# 4024_bin_counter.net
KiCad netlist of a schematic drawn in EAGLE
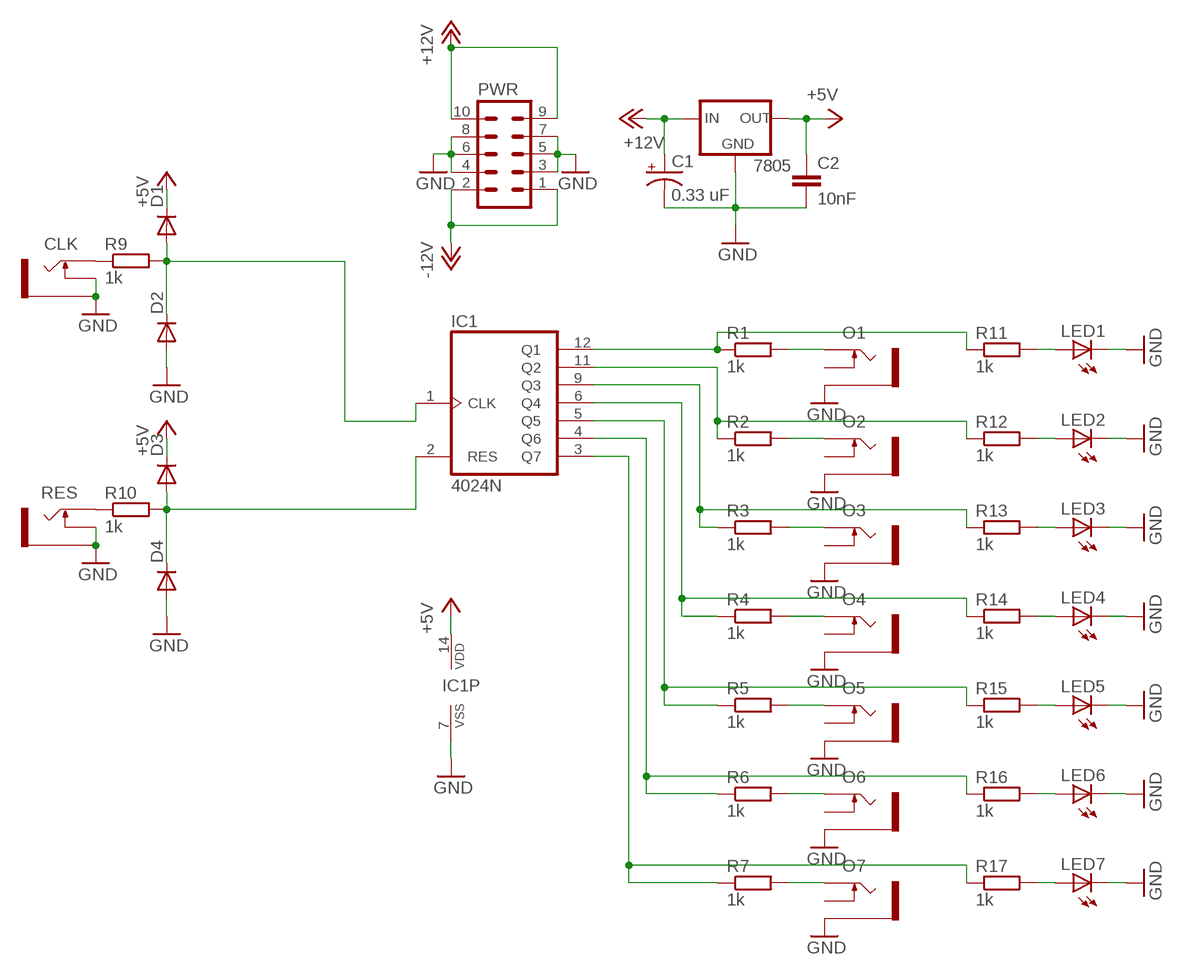
[diagram p0: schematic, sheet 1]

(export (version "E")
  (design (tool "Eeschema 10.0.6"))
  (components
    (comp (ref "7805")
      (value "78XXS")
      (footprint "eagle-import:78XXS")
      (libsource (lib "eagle-import") (part "78XXS"))
    )
    (comp (ref "C1")
      (value "0.33 uF")
      (footprint "eagle-import:E2,5-7")
      (libsource (lib "eagle-import") (part "CPOL-USE2.5-7"))
    )
    (comp (ref "C2")
      (value "10nF")
      (footprint "eagle-import:CAP-PTH-10MM")
      (libsource (lib "eagle-import") (part "10NF-PTH-10MM-10000V-1-%"))
    )
    (comp (ref "CLK")
      (value "THONKICONNNEW")
      (footprint "eagle-import:WQP-PJ301M-12_JACK")
      (libsource (lib "eagle-import") (part "THONKICONNNEW"))
    )
    (comp (ref "D1")
      (value "SMALL_DIODEDO35-7")
      (footprint "eagle-import:DO35-7")
      (libsource (lib "eagle-import") (part "SMALL_DIODEDO35-7"))
    )
    (comp (ref "D2")
      (value "SMALL_DIODEDO35-7")
      (footprint "eagle-import:DO35-7")
      (libsource (lib "eagle-import") (part "SMALL_DIODEDO35-7"))
    )
    (comp (ref "D3")
      (value "SMALL_DIODEDO35-7")
      (footprint "eagle-import:DO35-7")
      (libsource (lib "eagle-import") (part "SMALL_DIODEDO35-7"))
    )
    (comp (ref "D4")
      (value "SMALL_DIODEDO35-7")
      (footprint "eagle-import:DO35-7")
      (libsource (lib "eagle-import") (part "SMALL_DIODEDO35-7"))
    )
    (comp (ref "IC1")
      (value "4024N")
      (footprint "eagle-import:DIL14")
      (libsource (lib "eagle-import") (part "4024N"))
    )
    (comp (ref "LED1")
      (value "LED3MM")
      (footprint "eagle-import:LED3MM")
      (libsource (lib "eagle-import") (part "LED3MM"))
    )
    (comp (ref "LED2")
      (value "LED3MM")
      (footprint "eagle-import:LED3MM")
      (libsource (lib "eagle-import") (part "LED3MM"))
    )
    (comp (ref "LED3")
      (value "LED3MM")
      (footprint "eagle-import:LED3MM")
      (libsource (lib "eagle-import") (part "LED3MM"))
    )
    (comp (ref "LED4")
      (value "LED3MM")
      (footprint "eagle-import:LED3MM")
      (libsource (lib "eagle-import") (part "LED3MM"))
    )
    (comp (ref "LED5")
      (value "LED3MM")
      (footprint "eagle-import:LED3MM")
      (libsource (lib "eagle-import") (part "LED3MM"))
    )
    (comp (ref "LED6")
      (value "LED3MM")
      (footprint "eagle-import:LED3MM")
      (libsource (lib "eagle-import") (part "LED3MM"))
    )
    (comp (ref "LED7")
      (value "LED3MM")
      (footprint "eagle-import:LED3MM")
      (libsource (lib "eagle-import") (part "LED3MM"))
    )
    (comp (ref "O1")
      (value "THONKICONNNEW")
      (footprint "eagle-import:WQP-PJ301M-12_JACK")
      (libsource (lib "eagle-import") (part "THONKICONNNEW"))
    )
    (comp (ref "O2")
      (value "THONKICONNNEW")
      (footprint "eagle-import:WQP-PJ301M-12_JACK")
      (libsource (lib "eagle-import") (part "THONKICONNNEW"))
    )
    (comp (ref "O3")
      (value "THONKICONNNEW")
      (footprint "eagle-import:WQP-PJ301M-12_JACK")
      (libsource (lib "eagle-import") (part "THONKICONNNEW"))
    )
    (comp (ref "O4")
      (value "THONKICONNNEW")
      (footprint "eagle-import:WQP-PJ301M-12_JACK")
      (libsource (lib "eagle-import") (part "THONKICONNNEW"))
    )
    (comp (ref "O5")
      (value "THONKICONNNEW")
      (footprint "eagle-import:WQP-PJ301M-12_JACK")
      (libsource (lib "eagle-import") (part "THONKICONNNEW"))
    )
    (comp (ref "O6")
      (value "THONKICONNNEW")
      (footprint "eagle-import:WQP-PJ301M-12_JACK")
      (libsource (lib "eagle-import") (part "THONKICONNNEW"))
    )
    (comp (ref "O7")
      (value "THONKICONNNEW")
      (footprint "eagle-import:WQP-PJ301M-12_JACK")
      (libsource (lib "eagle-import") (part "THONKICONNNEW"))
    )
    (comp (ref "PWR")
      (value "EURO_POWER_HEADERFAT_PADS")
      (footprint "eagle-import:EURO_PWR_HEADER_FAT")
      (libsource (lib "eagle-import") (part "EURO_POWER_HEADERFAT_PADS"))
    )
    (comp (ref "R1")
      (value "1k")
      (footprint "eagle-import:7MM_RESISTOR")
      (libsource (lib "eagle-import") (part "RESISTOR7MM"))
    )
    (comp (ref "R2")
      (value "1k")
      (footprint "eagle-import:7MM_RESISTOR")
      (libsource (lib "eagle-import") (part "RESISTOR7MM"))
    )
    (comp (ref "R3")
      (value "1k")
      (footprint "eagle-import:7MM_RESISTOR")
      (libsource (lib "eagle-import") (part "RESISTOR7MM"))
    )
    (comp (ref "R4")
      (value "1k")
      (footprint "eagle-import:7MM_RESISTOR")
      (libsource (lib "eagle-import") (part "RESISTOR7MM"))
    )
    (comp (ref "R5")
      (value "1k")
      (footprint "eagle-import:7MM_RESISTOR")
      (libsource (lib "eagle-import") (part "RESISTOR7MM"))
    )
    (comp (ref "R6")
      (value "1k")
      (footprint "eagle-import:7MM_RESISTOR")
      (libsource (lib "eagle-import") (part "RESISTOR7MM"))
    )
    (comp (ref "R7")
      (value "1k")
      (footprint "eagle-import:7MM_RESISTOR")
      (libsource (lib "eagle-import") (part "RESISTOR7MM"))
    )
    (comp (ref "R9")
      (value "1k")
      (footprint "eagle-import:7MM_RESISTOR")
      (libsource (lib "eagle-import") (part "RESISTOR7MM"))
    )
    (comp (ref "R10")
      (value "1k")
      (footprint "eagle-import:7MM_RESISTOR")
      (libsource (lib "eagle-import") (part "RESISTOR7MM"))
    )
    (comp (ref "R11")
      (value "1k")
      (footprint "eagle-import:7MM_RESISTOR")
      (libsource (lib "eagle-import") (part "RESISTOR7MM"))
    )
    (comp (ref "R12")
      (value "1k")
      (footprint "eagle-import:7MM_RESISTOR")
      (libsource (lib "eagle-import") (part "RESISTOR7MM"))
    )
    (comp (ref "R13")
      (value "1k")
      (footprint "eagle-import:7MM_RESISTOR")
      (libsource (lib "eagle-import") (part "RESISTOR7MM"))
    )
    (comp (ref "R14")
      (value "1k")
      (footprint "eagle-import:7MM_RESISTOR")
      (libsource (lib "eagle-import") (part "RESISTOR7MM"))
    )
    (comp (ref "R15")
      (value "1k")
      (footprint "eagle-import:7MM_RESISTOR")
      (libsource (lib "eagle-import") (part "RESISTOR7MM"))
    )
    (comp (ref "R16")
      (value "1k")
      (footprint "eagle-import:7MM_RESISTOR")
      (libsource (lib "eagle-import") (part "RESISTOR7MM"))
    )
    (comp (ref "R17")
      (value "1k")
      (footprint "eagle-import:7MM_RESISTOR")
      (libsource (lib "eagle-import") (part "RESISTOR7MM"))
    )
    (comp (ref "RES")
      (value "THONKICONNNEW")
      (footprint "eagle-import:WQP-PJ301M-12_JACK")
      (libsource (lib "eagle-import") (part "THONKICONNNEW"))
    )
  )
  (nets
    (net (code "1") (name "+5V") (class "Default")
      (node (ref "7805") (pin "OUT") (pinfunction "OUT_OUT") (pintype "passive"))
      (node (ref "C2") (pin "1") (pinfunction "1_1") (pintype "passive"))
      (node (ref "D1") (pin "C") (pinfunction "C_C") (pintype "passive"))
      (node (ref "D3") (pin "C") (pinfunction "C_C") (pintype "passive"))
      (node (ref "IC1") (pin "14") (pinfunction "VDD_14") (pintype "power_in"))
    )
    (net (code "2") (name "+12V") (class "Default")
      (node (ref "7805") (pin "IN") (pinfunction "IN_IN") (pintype "input"))
      (node (ref "C1") (pin "+") (pinfunction "+_+") (pintype "passive"))
      (node (ref "PWR") (pin "10") (pinfunction "10_10") (pintype "passive"))
      (node (ref "PWR") (pin "9") (pinfunction "9_9") (pintype "passive"))
    )
    (net (code "3") (name "-12V") (class "Default")
      (node (ref "PWR") (pin "1") (pinfunction "1_1") (pintype "passive"))
      (node (ref "PWR") (pin "2") (pinfunction "2_2") (pintype "passive"))
    )
    (net (code "4") (name "GND") (class "Default")
      (node (ref "7805") (pin "GND") (pinfunction "GND_GND") (pintype "input"))
      (node (ref "C1") (pin "-") (pinfunction "-_-") (pintype "passive"))
      (node (ref "C2") (pin "2") (pinfunction "2_2") (pintype "passive"))
      (node (ref "CLK") (pin "P$2_SWITCH") (pinfunction "SWITCH_P$2_SWITCH") (pintype "passive"))
      (node (ref "CLK") (pin "P$3_SLEEVE") (pinfunction "SLEEVE_P$3_SLEEVE") (pintype "passive"))
      (node (ref "D2") (pin "A") (pinfunction "A_A") (pintype "passive"))
      (node (ref "D4") (pin "A") (pinfunction "A_A") (pintype "passive"))
      (node (ref "IC1") (pin "7") (pinfunction "VSS_7") (pintype "power_in"))
      (node (ref "LED1") (pin "K") (pinfunction "C_K") (pintype "passive"))
      (node (ref "LED2") (pin "K") (pinfunction "C_K") (pintype "passive"))
      (node (ref "LED3") (pin "K") (pinfunction "C_K") (pintype "passive"))
      (node (ref "LED4") (pin "K") (pinfunction "C_K") (pintype "passive"))
      (node (ref "LED5") (pin "K") (pinfunction "C_K") (pintype "passive"))
      (node (ref "LED6") (pin "K") (pinfunction "C_K") (pintype "passive"))
      (node (ref "LED7") (pin "K") (pinfunction "C_K") (pintype "passive"))
      (node (ref "O1") (pin "P$3_SLEEVE") (pinfunction "SLEEVE_P$3_SLEEVE") (pintype "passive"))
      (node (ref "O2") (pin "P$3_SLEEVE") (pinfunction "SLEEVE_P$3_SLEEVE") (pintype "passive"))
      (node (ref "O3") (pin "P$3_SLEEVE") (pinfunction "SLEEVE_P$3_SLEEVE") (pintype "passive"))
      (node (ref "O4") (pin "P$3_SLEEVE") (pinfunction "SLEEVE_P$3_SLEEVE") (pintype "passive"))
      (node (ref "O5") (pin "P$3_SLEEVE") (pinfunction "SLEEVE_P$3_SLEEVE") (pintype "passive"))
      (node (ref "O6") (pin "P$3_SLEEVE") (pinfunction "SLEEVE_P$3_SLEEVE") (pintype "passive"))
      (node (ref "O7") (pin "P$3_SLEEVE") (pinfunction "SLEEVE_P$3_SLEEVE") (pintype "passive"))
      (node (ref "PWR") (pin "3") (pinfunction "3_3") (pintype "passive"))
      (node (ref "PWR") (pin "4") (pinfunction "4_4") (pintype "passive"))
      (node (ref "PWR") (pin "5") (pinfunction "5_5") (pintype "passive"))
      (node (ref "PWR") (pin "6") (pinfunction "6_6") (pintype "passive"))
      (node (ref "PWR") (pin "7") (pinfunction "7_7") (pintype "passive"))
      (node (ref "PWR") (pin "8") (pinfunction "8_8") (pintype "passive"))
      (node (ref "RES") (pin "P$2_SWITCH") (pinfunction "SWITCH_P$2_SWITCH") (pintype "passive"))
      (node (ref "RES") (pin "P$3_SLEEVE") (pinfunction "SLEEVE_P$3_SLEEVE") (pintype "passive"))
    )
    (net (code "5") (name "Net-(CLK-TIP)") (class "Default")
      (node (ref "CLK") (pin "P$1_TIP") (pinfunction "TIP_P$1_TIP") (pintype "passive"))
      (node (ref "R9") (pin "1") (pinfunction "1_1") (pintype "passive"))
    )
    (net (code "6") (name "Net-(IC1A-CLK)") (class "Default")
      (node (ref "D1") (pin "A") (pinfunction "A_A") (pintype "passive"))
      (node (ref "D2") (pin "C") (pinfunction "C_C") (pintype "passive"))
      (node (ref "IC1") (pin "1") (pinfunction "CLK_1") (pintype "input"))
      (node (ref "R9") (pin "2") (pinfunction "2_2") (pintype "passive"))
    )
    (net (code "7") (name "Net-(IC1A-Q1)") (class "Default")
      (node (ref "IC1") (pin "12") (pinfunction "Q1_12") (pintype "output"))
      (node (ref "R1") (pin "1") (pinfunction "1_1") (pintype "passive"))
      (node (ref "R11") (pin "1") (pinfunction "1_1") (pintype "passive"))
    )
    (net (code "8") (name "Net-(IC1A-Q2)") (class "Default")
      (node (ref "IC1") (pin "11") (pinfunction "Q2_11") (pintype "output"))
      (node (ref "R12") (pin "1") (pinfunction "1_1") (pintype "passive"))
      (node (ref "R2") (pin "1") (pinfunction "1_1") (pintype "passive"))
    )
    (net (code "9") (name "Net-(IC1A-Q3)") (class "Default")
      (node (ref "IC1") (pin "9") (pinfunction "Q3_9") (pintype "output"))
      (node (ref "R13") (pin "1") (pinfunction "1_1") (pintype "passive"))
      (node (ref "R3") (pin "1") (pinfunction "1_1") (pintype "passive"))
    )
    (net (code "10") (name "Net-(IC1A-Q4)") (class "Default")
      (node (ref "IC1") (pin "6") (pinfunction "Q4_6") (pintype "output"))
      (node (ref "R14") (pin "1") (pinfunction "1_1") (pintype "passive"))
      (node (ref "R4") (pin "1") (pinfunction "1_1") (pintype "passive"))
    )
    (net (code "11") (name "Net-(IC1A-Q5)") (class "Default")
      (node (ref "IC1") (pin "5") (pinfunction "Q5_5") (pintype "output"))
      (node (ref "R15") (pin "1") (pinfunction "1_1") (pintype "passive"))
      (node (ref "R5") (pin "1") (pinfunction "1_1") (pintype "passive"))
    )
    (net (code "12") (name "Net-(IC1A-Q6)") (class "Default")
      (node (ref "IC1") (pin "4") (pinfunction "Q6_4") (pintype "output"))
      (node (ref "R16") (pin "1") (pinfunction "1_1") (pintype "passive"))
      (node (ref "R6") (pin "1") (pinfunction "1_1") (pintype "passive"))
    )
    (net (code "13") (name "Net-(IC1A-Q7)") (class "Default")
      (node (ref "IC1") (pin "3") (pinfunction "Q7_3") (pintype "output"))
      (node (ref "R17") (pin "1") (pinfunction "1_1") (pintype "passive"))
      (node (ref "R7") (pin "1") (pinfunction "1_1") (pintype "passive"))
    )
    (net (code "14") (name "Net-(IC1A-RES)") (class "Default")
      (node (ref "D3") (pin "A") (pinfunction "A_A") (pintype "passive"))
      (node (ref "D4") (pin "C") (pinfunction "C_C") (pintype "passive"))
      (node (ref "IC1") (pin "2") (pinfunction "RES_2") (pintype "input"))
      (node (ref "R10") (pin "2") (pinfunction "2_2") (pintype "passive"))
    )
    (net (code "15") (name "Net-(LED1-PadA)") (class "Default")
      (node (ref "LED1") (pin "A") (pinfunction "A_A") (pintype "passive"))
      (node (ref "R11") (pin "2") (pinfunction "2_2") (pintype "passive"))
    )
    (net (code "16") (name "Net-(LED2-PadA)") (class "Default")
      (node (ref "LED2") (pin "A") (pinfunction "A_A") (pintype "passive"))
      (node (ref "R12") (pin "2") (pinfunction "2_2") (pintype "passive"))
    )
    (net (code "17") (name "Net-(LED3-PadA)") (class "Default")
      (node (ref "LED3") (pin "A") (pinfunction "A_A") (pintype "passive"))
      (node (ref "R13") (pin "2") (pinfunction "2_2") (pintype "passive"))
    )
    (net (code "18") (name "Net-(LED4-PadA)") (class "Default")
      (node (ref "LED4") (pin "A") (pinfunction "A_A") (pintype "passive"))
      (node (ref "R14") (pin "2") (pinfunction "2_2") (pintype "passive"))
    )
    (net (code "19") (name "Net-(LED5-PadA)") (class "Default")
      (node (ref "LED5") (pin "A") (pinfunction "A_A") (pintype "passive"))
      (node (ref "R15") (pin "2") (pinfunction "2_2") (pintype "passive"))
    )
    (net (code "20") (name "Net-(LED6-PadA)") (class "Default")
      (node (ref "LED6") (pin "A") (pinfunction "A_A") (pintype "passive"))
      (node (ref "R16") (pin "2") (pinfunction "2_2") (pintype "passive"))
    )
    (net (code "21") (name "Net-(LED7-PadA)") (class "Default")
      (node (ref "LED7") (pin "A") (pinfunction "A_A") (pintype "passive"))
      (node (ref "R17") (pin "2") (pinfunction "2_2") (pintype "passive"))
    )
    (net (code "22") (name "Net-(O1-TIP)") (class "Default")
      (node (ref "O1") (pin "P$1_TIP") (pinfunction "TIP_P$1_TIP") (pintype "passive"))
      (node (ref "R1") (pin "2") (pinfunction "2_2") (pintype "passive"))
    )
    (net (code "23") (name "Net-(O2-TIP)") (class "Default")
      (node (ref "O2") (pin "P$1_TIP") (pinfunction "TIP_P$1_TIP") (pintype "passive"))
      (node (ref "R2") (pin "2") (pinfunction "2_2") (pintype "passive"))
    )
    (net (code "24") (name "Net-(O3-TIP)") (class "Default")
      (node (ref "O3") (pin "P$1_TIP") (pinfunction "TIP_P$1_TIP") (pintype "passive"))
      (node (ref "R3") (pin "2") (pinfunction "2_2") (pintype "passive"))
    )
    (net (code "25") (name "Net-(O4-TIP)") (class "Default")
      (node (ref "O4") (pin "P$1_TIP") (pinfunction "TIP_P$1_TIP") (pintype "passive"))
      (node (ref "R4") (pin "2") (pinfunction "2_2") (pintype "passive"))
    )
    (net (code "26") (name "Net-(O5-TIP)") (class "Default")
      (node (ref "O5") (pin "P$1_TIP") (pinfunction "TIP_P$1_TIP") (pintype "passive"))
      (node (ref "R5") (pin "2") (pinfunction "2_2") (pintype "passive"))
    )
    (net (code "27") (name "Net-(O6-TIP)") (class "Default")
      (node (ref "O6") (pin "P$1_TIP") (pinfunction "TIP_P$1_TIP") (pintype "passive"))
      (node (ref "R6") (pin "2") (pinfunction "2_2") (pintype "passive"))
    )
    (net (code "28") (name "Net-(O7-TIP)") (class "Default")
      (node (ref "O7") (pin "P$1_TIP") (pinfunction "TIP_P$1_TIP") (pintype "passive"))
      (node (ref "R7") (pin "2") (pinfunction "2_2") (pintype "passive"))
    )
    (net (code "29") (name "Net-(RES-TIP)") (class "Default")
      (node (ref "R10") (pin "1") (pinfunction "1_1") (pintype "passive"))
      (node (ref "RES") (pin "P$1_TIP") (pinfunction "TIP_P$1_TIP") (pintype "passive"))
    )
    (net (code "30") (name "unconnected-(O1-SWITCH-PadP$2_SWITCH)") (class "Default")
      (node (ref "O1") (pin "P$2_SWITCH") (pinfunction "SWITCH_P$2_SWITCH") (pintype "passive"))
    )
    (net (code "31") (name "unconnected-(O2-SWITCH-PadP$2_SWITCH)") (class "Default")
      (node (ref "O2") (pin "P$2_SWITCH") (pinfunction "SWITCH_P$2_SWITCH") (pintype "passive"))
    )
    (net (code "32") (name "unconnected-(O3-SWITCH-PadP$2_SWITCH)") (class "Default")
      (node (ref "O3") (pin "P$2_SWITCH") (pinfunction "SWITCH_P$2_SWITCH") (pintype "passive"))
    )
    (net (code "33") (name "unconnected-(O4-SWITCH-PadP$2_SWITCH)") (class "Default")
      (node (ref "O4") (pin "P$2_SWITCH") (pinfunction "SWITCH_P$2_SWITCH") (pintype "passive"))
    )
    (net (code "34") (name "unconnected-(O5-SWITCH-PadP$2_SWITCH)") (class "Default")
      (node (ref "O5") (pin "P$2_SWITCH") (pinfunction "SWITCH_P$2_SWITCH") (pintype "passive"))
    )
    (net (code "35") (name "unconnected-(O6-SWITCH-PadP$2_SWITCH)") (class "Default")
      (node (ref "O6") (pin "P$2_SWITCH") (pinfunction "SWITCH_P$2_SWITCH") (pintype "passive"))
    )
    (net (code "36") (name "unconnected-(O7-SWITCH-PadP$2_SWITCH)") (class "Default")
      (node (ref "O7") (pin "P$2_SWITCH") (pinfunction "SWITCH_P$2_SWITCH") (pintype "passive"))
    )
  )
)
